# System_VoltageControl.net
KiCad netlist of a schematic drawn in Altium Designer
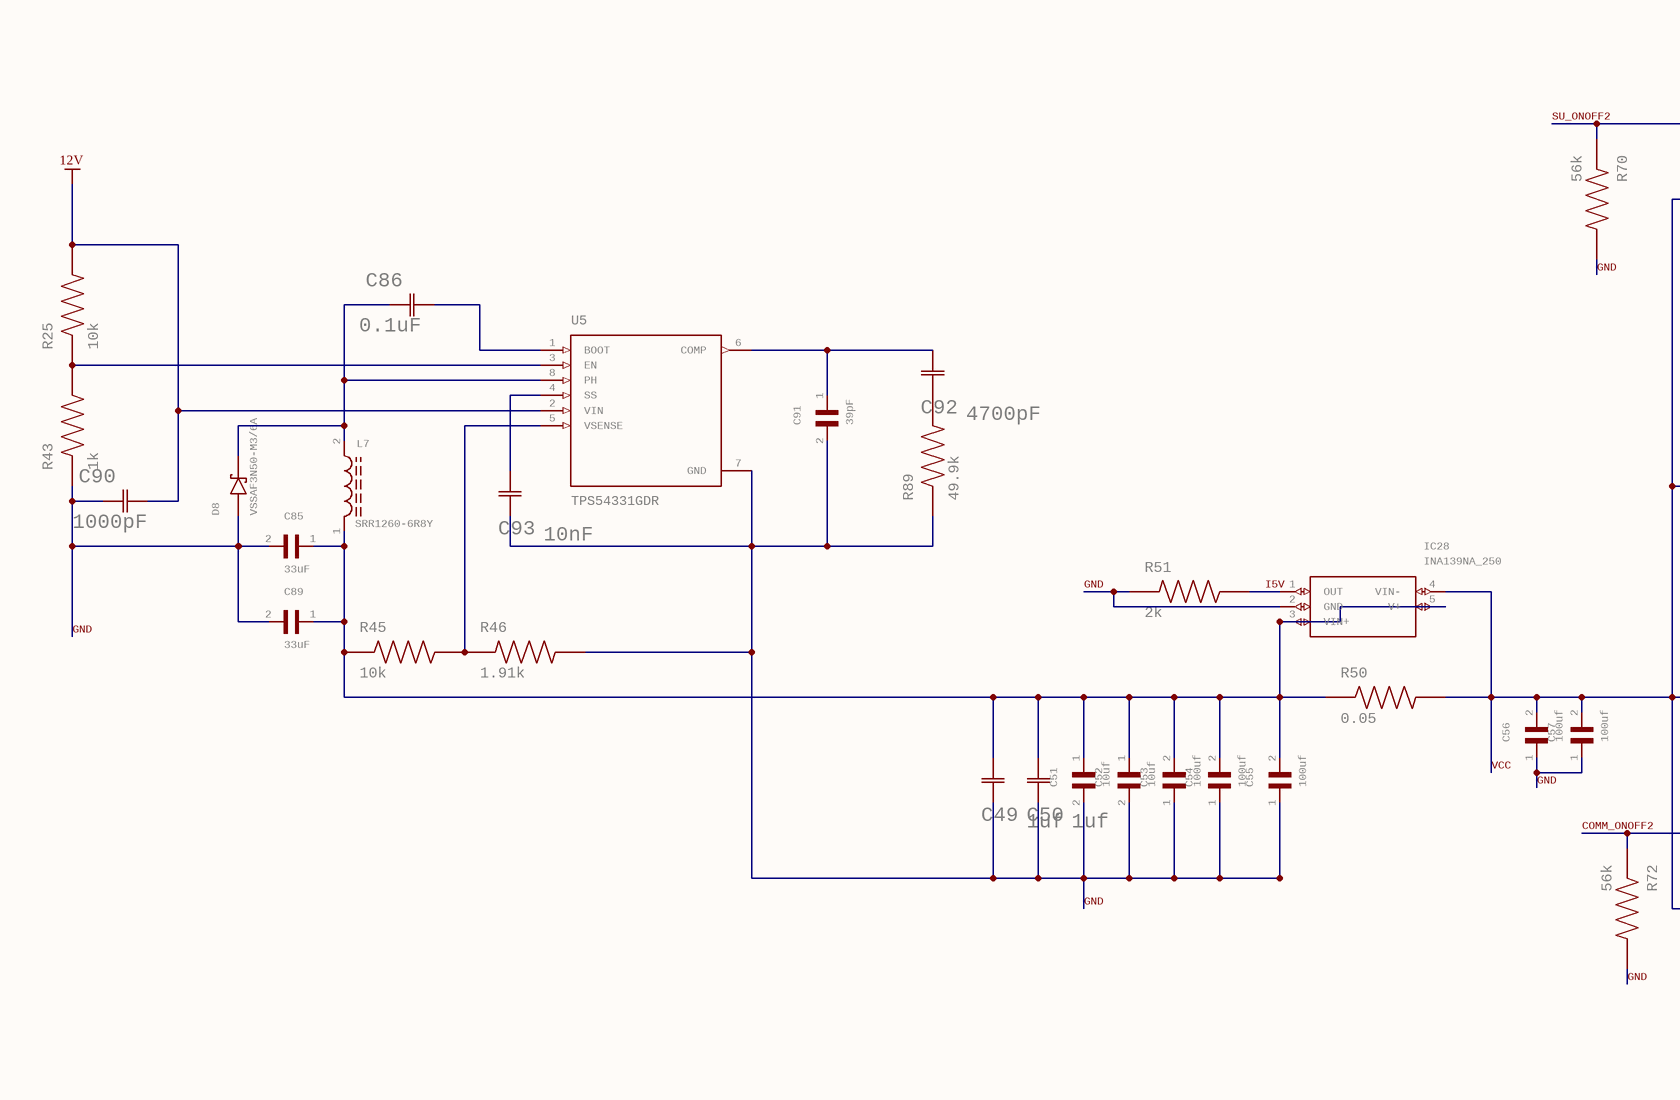
[diagram p0: System_VoltageControl.SchDoc, top left]
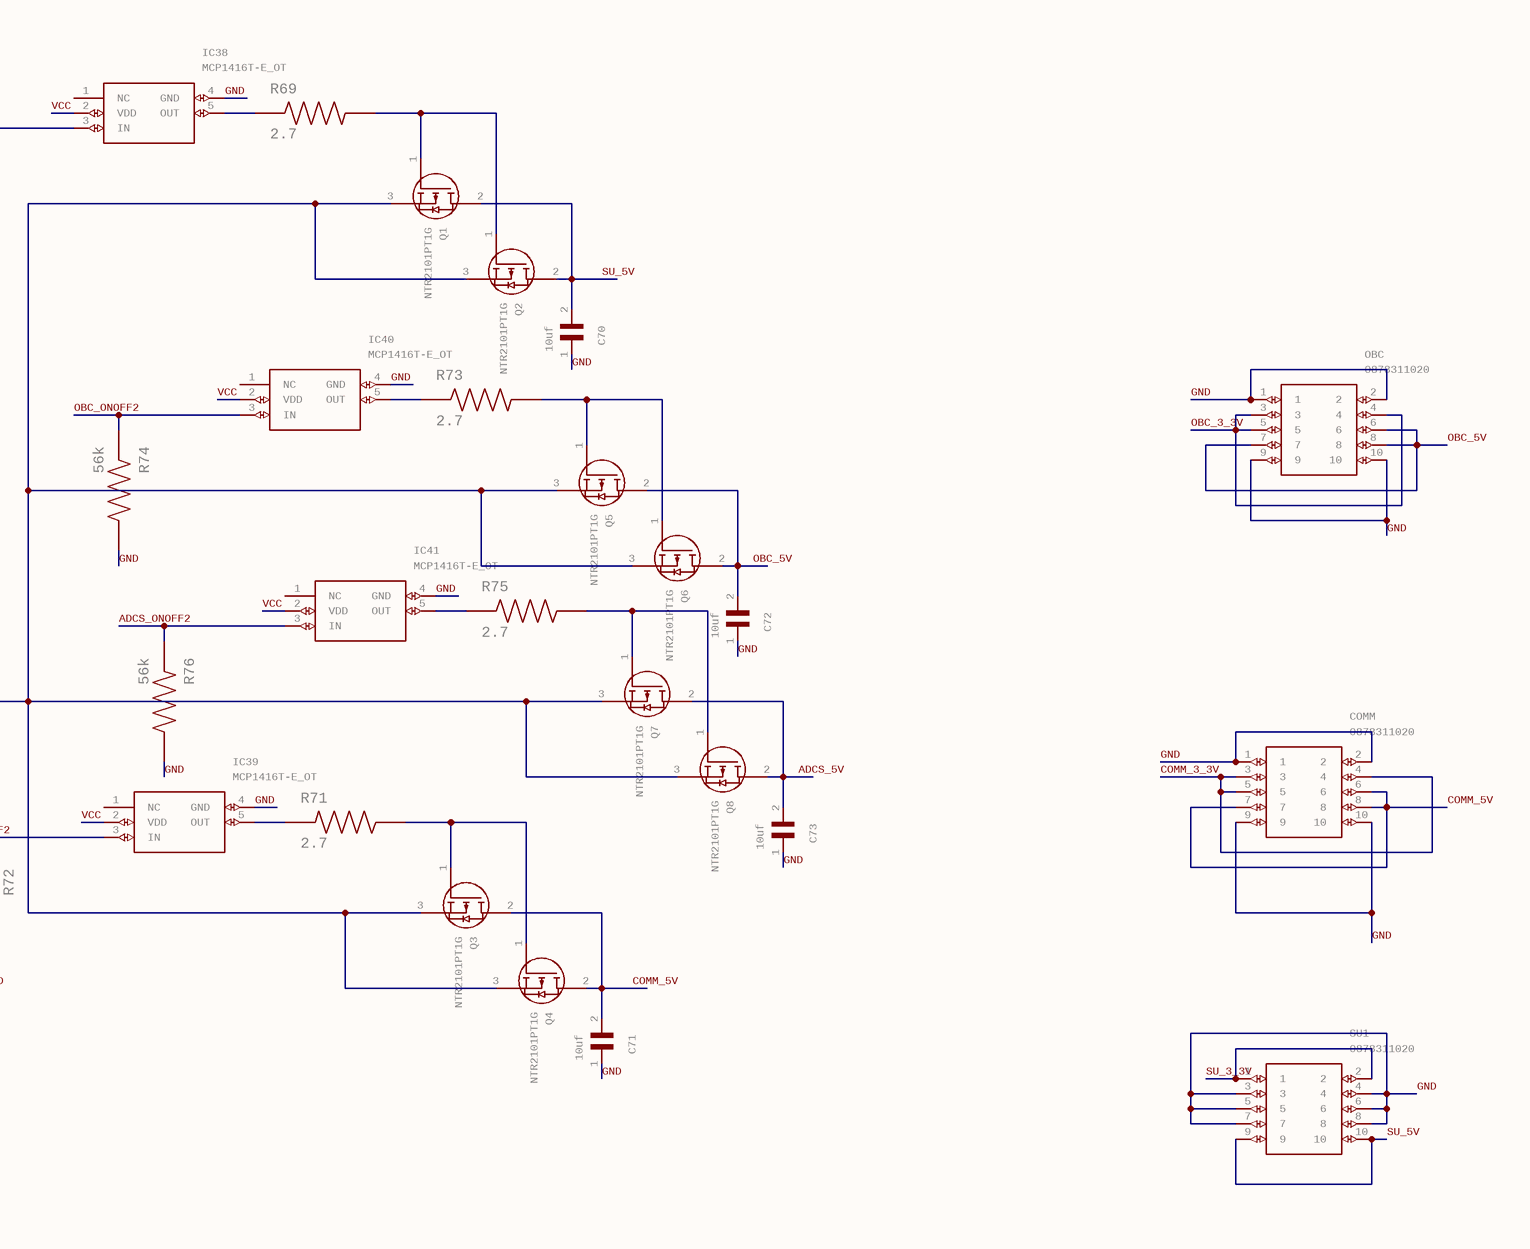
[diagram p1: System_VoltageControl.SchDoc, top right]
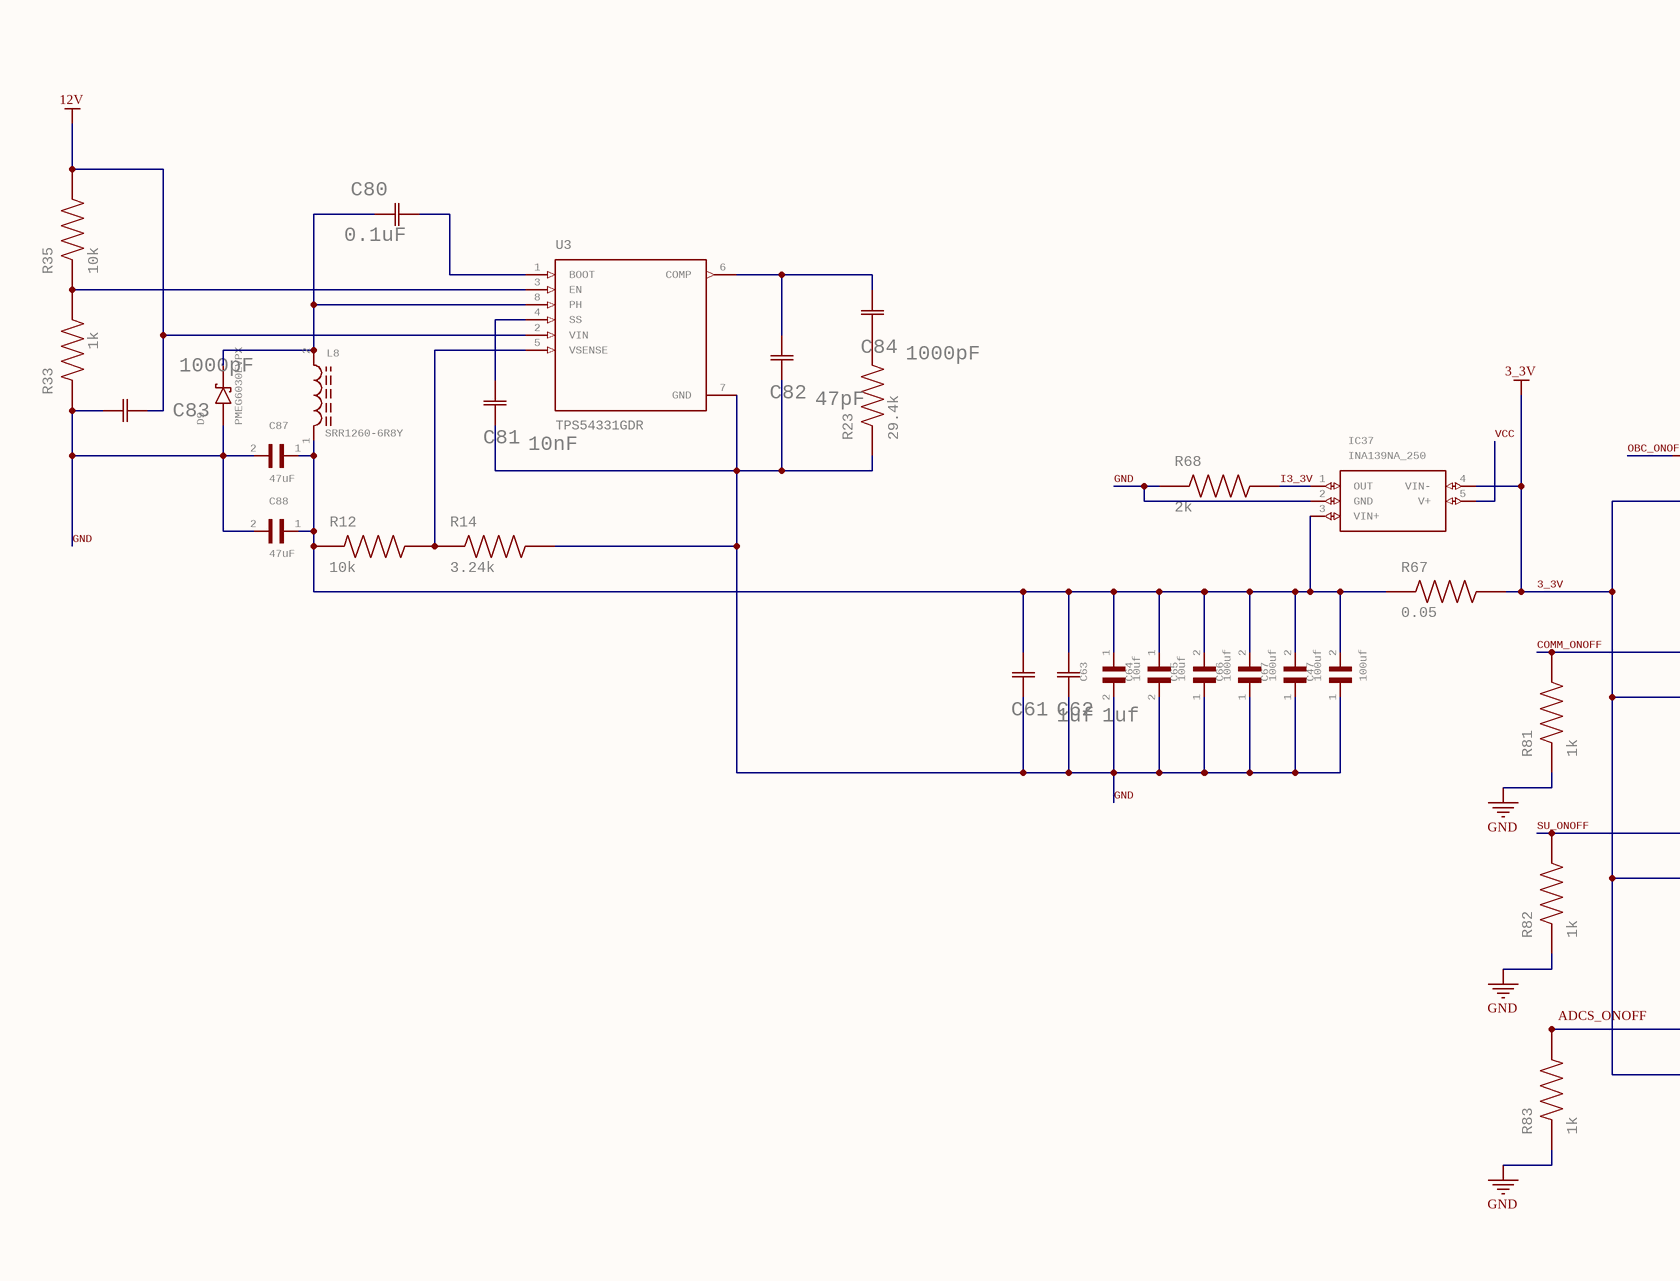
[diagram p2: System_VoltageControl.SchDoc, bottom left]
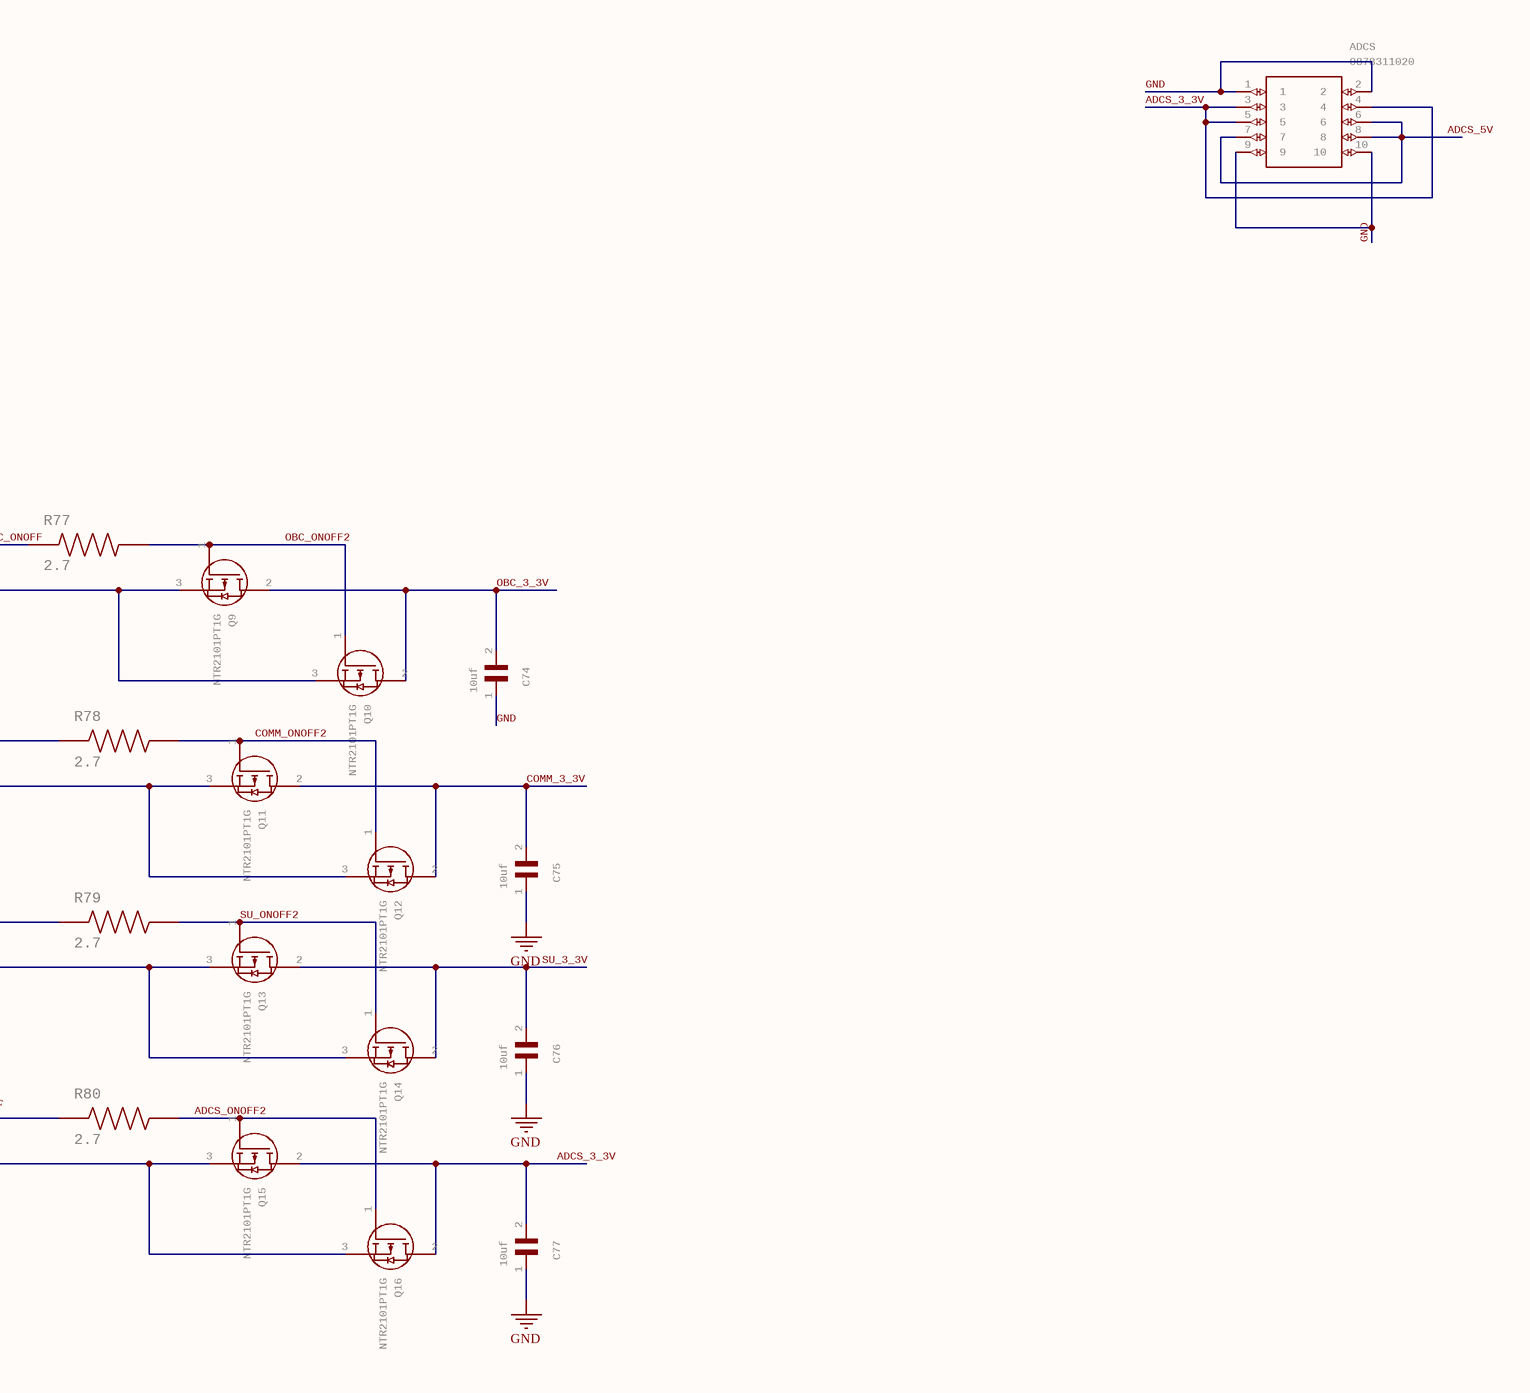
[diagram p3: System_VoltageControl.SchDoc, bottom right]

(export (version "E")
  (design (tool "Eeschema 10.0.6"))
  (components
    (comp (ref "ADCS")
      (value "0878311020")
      (footprint "SHDR10W55P200_2X5_1265X630X640")
      (description "Headers & Wire Housings 2.00MM HDR 02X05P VT TH 15AU   Source:  Datasheet")
      (libsource (lib "0878311020") (part "0878311020"))
    )
    (comp (ref "C47")
      (value "100uf")
      (footprint "CAPC3225X280N")
      (fields
        (field (name "DIGI-KEY_PART_NUMBER") "DIGI-KEY_PART_NUMBER")
        (field (name "MF") "KEMET")
        (field (name "MP") "C1210C107M4PAC7800")
      )
      (libsource (lib "Cap 100uf 16v") (part "C1210C107M4PAC7800"))
    )
    (comp (ref "C49")
      (value "1uf")
      (footprint "YAG_CC0603_YAG")
      (fields (field (name "MANUFACTURER_PART_NUMBER") "CC0603KRX7R7BB105"))
      (libsource (lib "Cap 1uf") (part "CC0603KRX7R7BB105"))
    )
    (comp (ref "C50")
      (value "1uf")
      (footprint "YAG_CC0603_YAG")
      (fields (field (name "MANUFACTURER_PART_NUMBER") "CC0603KRX7R7BB105"))
      (libsource (lib "Cap 1uf") (part "CC0603KRX7R7BB105"))
    )
    (comp (ref "C51")
      (value "10uf")
      (footprint "CAPC2012X70")
      (description "KC 10ÂµF 0805 10% 16V X5R")
      (fields (field (name "DIGI-KEY_PART_NUMBER") "311-1865-1-ND") (field (name "MF") "Yageo"))
      (libsource (lib "") (part "CC0805KKX5R7BB106_1"))
    )
    (comp (ref "C52")
      (value "10uf")
      (footprint "CAPC2012X70")
      (description "KC 10ÂµF 0805 10% 16V X5R")
      (fields (field (name "DIGI-KEY_PART_NUMBER") "311-1865-1-ND") (field (name "MF") "Yageo"))
      (libsource (lib "") (part "CC0805KKX5R7BB106_1"))
    )
    (comp (ref "C53")
      (value "100uf")
      (footprint "CAPC3225X280N")
      (fields
        (field (name "DIGI-KEY_PART_NUMBER") "DIGI-KEY_PART_NUMBER")
        (field (name "MF") "KEMET")
        (field (name "MP") "C1210C107M4PAC7800")
      )
      (libsource (lib "Cap 100uf 16v") (part "C1210C107M4PAC7800"))
    )
    (comp (ref "C54")
      (value "100uf")
      (footprint "CAPC3225X280N")
      (fields
        (field (name "DIGI-KEY_PART_NUMBER") "DIGI-KEY_PART_NUMBER")
        (field (name "MF") "KEMET")
        (field (name "MP") "C1210C107M4PAC7800")
      )
      (libsource (lib "Cap 100uf 16v") (part "C1210C107M4PAC7800"))
    )
    (comp (ref "C55")
      (value "100uf")
      (footprint "CAPC3225X280N")
      (fields
        (field (name "DIGI-KEY_PART_NUMBER") "DIGI-KEY_PART_NUMBER")
        (field (name "MF") "KEMET")
        (field (name "MP") "C1210C107M4PAC7800")
      )
      (libsource (lib "Cap 100uf 16v") (part "C1210C107M4PAC7800"))
    )
    (comp (ref "C56")
      (value "100uf")
      (footprint "CAPC3225X280N")
      (fields
        (field (name "DIGI-KEY_PART_NUMBER") "DIGI-KEY_PART_NUMBER")
        (field (name "MF") "KEMET")
        (field (name "MP") "C1210C107M4PAC7800")
      )
      (libsource (lib "Cap 100uf 16v") (part "C1210C107M4PAC7800"))
    )
    (comp (ref "C57")
      (value "100uf")
      (footprint "CAPC3225X280N")
      (fields
        (field (name "DIGI-KEY_PART_NUMBER") "DIGI-KEY_PART_NUMBER")
        (field (name "MF") "KEMET")
        (field (name "MP") "C1210C107M4PAC7800")
      )
      (libsource (lib "Cap 100uf 16v") (part "C1210C107M4PAC7800"))
    )
    (comp (ref "C61")
      (value "1uf")
      (footprint "YAG_CC0603_YAG")
      (fields (field (name "MANUFACTURER_PART_NUMBER") "CC0603KRX7R7BB105"))
      (libsource (lib "Cap 1uf") (part "CC0603KRX7R7BB105"))
    )
    (comp (ref "C62")
      (value "1uf")
      (footprint "YAG_CC0603_YAG")
      (fields (field (name "MANUFACTURER_PART_NUMBER") "CC0603KRX7R7BB105"))
      (libsource (lib "Cap 1uf") (part "CC0603KRX7R7BB105"))
    )
    (comp (ref "C63")
      (value "10uf")
      (footprint "CAPC2012X70")
      (description "KC 10ÂµF 0805 10% 16V X5R")
      (fields (field (name "DIGI-KEY_PART_NUMBER") "311-1865-1-ND") (field (name "MF") "Yageo"))
      (libsource (lib "") (part "CC0805KKX5R7BB106_1"))
    )
    (comp (ref "C64")
      (value "10uf")
      (footprint "CAPC2012X70")
      (description "KC 10ÂµF 0805 10% 16V X5R")
      (fields (field (name "DIGI-KEY_PART_NUMBER") "311-1865-1-ND") (field (name "MF") "Yageo"))
      (libsource (lib "") (part "CC0805KKX5R7BB106_1"))
    )
    (comp (ref "C65")
      (value "100uf")
      (footprint "CAPC3225X280N")
      (fields
        (field (name "DIGI-KEY_PART_NUMBER") "DIGI-KEY_PART_NUMBER")
        (field (name "MF") "KEMET")
        (field (name "MP") "C1210C107M4PAC7800")
      )
      (libsource (lib "Cap 100uf 16v") (part "C1210C107M4PAC7800"))
    )
    (comp (ref "C66")
      (value "100uf")
      (footprint "CAPC3225X280N")
      (fields
        (field (name "DIGI-KEY_PART_NUMBER") "DIGI-KEY_PART_NUMBER")
        (field (name "MF") "KEMET")
        (field (name "MP") "C1210C107M4PAC7800")
      )
      (libsource (lib "Cap 100uf 16v") (part "C1210C107M4PAC7800"))
    )
    (comp (ref "C67")
      (value "100uf")
      (footprint "CAPC3225X280N")
      (fields
        (field (name "DIGI-KEY_PART_NUMBER") "DIGI-KEY_PART_NUMBER")
        (field (name "MF") "KEMET")
        (field (name "MP") "C1210C107M4PAC7800")
      )
      (libsource (lib "Cap 100uf 16v") (part "C1210C107M4PAC7800"))
    )
    (comp (ref "C70")
      (value "10uf")
      (footprint "CAPC2012X70")
      (description "KC 10ÂµF 0805 10% 16V X5R")
      (fields (field (name "DIGI-KEY_PART_NUMBER") "311-1865-1-ND") (field (name "MF") "Yageo"))
      (libsource (lib "") (part "CC0805KKX5R7BB106_2"))
    )
    (comp (ref "C71")
      (value "10uf")
      (footprint "CAPC2012X70")
      (description "KC 10ÂµF 0805 10% 16V X5R")
      (fields (field (name "DIGI-KEY_PART_NUMBER") "311-1865-1-ND") (field (name "MF") "Yageo"))
      (libsource (lib "") (part "CC0805KKX5R7BB106_2"))
    )
    (comp (ref "C72")
      (value "10uf")
      (footprint "CAPC2012X70")
      (description "KC 10ÂµF 0805 10% 16V X5R")
      (fields (field (name "DIGI-KEY_PART_NUMBER") "311-1865-1-ND") (field (name "MF") "Yageo"))
      (libsource (lib "") (part "CC0805KKX5R7BB106_2"))
    )
    (comp (ref "C73")
      (value "10uf")
      (footprint "CAPC2012X70")
      (description "KC 10ÂµF 0805 10% 16V X5R")
      (fields (field (name "DIGI-KEY_PART_NUMBER") "311-1865-1-ND") (field (name "MF") "Yageo"))
      (libsource (lib "") (part "CC0805KKX5R7BB106_2"))
    )
    (comp (ref "C74")
      (value "10uf")
      (footprint "CAPC2012X70")
      (description "KC 10ÂµF 0805 10% 16V X5R")
      (fields (field (name "DIGI-KEY_PART_NUMBER") "311-1865-1-ND") (field (name "MF") "Yageo"))
      (libsource (lib "") (part "CC0805KKX5R7BB106_2"))
    )
    (comp (ref "C75")
      (value "10uf")
      (footprint "CAPC2012X70")
      (description "KC 10ÂµF 0805 10% 16V X5R")
      (fields (field (name "DIGI-KEY_PART_NUMBER") "311-1865-1-ND") (field (name "MF") "Yageo"))
      (libsource (lib "") (part "CC0805KKX5R7BB106_2"))
    )
    (comp (ref "C76")
      (value "10uf")
      (footprint "CAPC2012X70")
      (description "KC 10ÂµF 0805 10% 16V X5R")
      (fields (field (name "DIGI-KEY_PART_NUMBER") "311-1865-1-ND") (field (name "MF") "Yageo"))
      (libsource (lib "") (part "CC0805KKX5R7BB106_2"))
    )
    (comp (ref "C77")
      (value "10uf")
      (footprint "CAPC2012X70")
      (description "KC 10ÂµF 0805 10% 16V X5R")
      (fields (field (name "DIGI-KEY_PART_NUMBER") "311-1865-1-ND") (field (name "MF") "Yageo"))
      (libsource (lib "") (part "CC0805KKX5R7BB106_2"))
    )
    (comp (ref "C80")
      (value "0.1uF")
      (footprint "CC0603N_YAG")
      (fields (field (name "MANUFACTURER_PART_NUMBER") "CC0603KRX7R7BB104"))
      (libsource (lib "Cap 0.1uf") (part "CC0603KRX7R7BB104"))
    )
    (comp (ref "C81")
      (value "10nF")
      (footprint "CC0603N_YAG")
      (fields (field (name "MANUFACTURER_PART_NUMBER") "CC0603KRX7R7BB104"))
      (libsource (lib "Cap 0.1uf") (part "CC0603KRX7R7BB104"))
    )
    (comp (ref "C82")
      (value "47pF")
      (footprint "CC0603N_YAG")
      (fields (field (name "MANUFACTURER_PART_NUMBER") "CC0603KRX7R7BB104"))
      (libsource (lib "Cap 0.1uf") (part "CC0603KRX7R7BB104"))
    )
    (comp (ref "C83")
      (value "1000pF")
      (footprint "CC0603N_YAG")
      (fields (field (name "MANUFACTURER_PART_NUMBER") "CC0603KRX7R7BB104"))
      (libsource (lib "Cap 0.1uf") (part "CC0603KRX7R7BB104"))
    )
    (comp (ref "C84")
      (value "1000pF")
      (footprint "CC0603N_YAG")
      (fields (field (name "MANUFACTURER_PART_NUMBER") "CC0603KRX7R7BB104"))
      (libsource (lib "Cap 0.1uf") (part "CC0603KRX7R7BB104"))
    )
    (comp (ref "C85")
      (value "33uF")
      (footprint "CAPC2012X70")
      (description "KC 10ÂµF 0805 10% 16V X5R")
      (fields (field (name "DIGI-KEY_PART_NUMBER") "311-1865-1-ND") (field (name "MF") "Yageo"))
      (libsource (lib "Cap 10uf") (part "CC0805KKX5R7BB106"))
    )
    (comp (ref "C86")
      (value "0.1uF")
      (footprint "CC0603N_YAG")
      (fields (field (name "MANUFACTURER_PART_NUMBER") "CC0603KRX7R7BB104"))
      (libsource (lib "Cap 0.1uf") (part "CC0603KRX7R7BB104"))
    )
    (comp (ref "C87")
      (value "47uF")
      (footprint "CAPC2012X70")
      (description "KC 10ÂµF 0805 10% 16V X5R")
      (fields (field (name "DIGI-KEY_PART_NUMBER") "311-1865-1-ND") (field (name "MF") "Yageo"))
      (libsource (lib "Cap 10uf") (part "CC0805KKX5R7BB106"))
    )
    (comp (ref "C88")
      (value "47uF")
      (footprint "CAPC2012X70")
      (description "KC 10ÂµF 0805 10% 16V X5R")
      (fields (field (name "DIGI-KEY_PART_NUMBER") "311-1865-1-ND") (field (name "MF") "Yageo"))
      (libsource (lib "Cap 10uf") (part "CC0805KKX5R7BB106"))
    )
    (comp (ref "C89")
      (value "33uF")
      (footprint "CAPC2012X70")
      (description "KC 10ÂµF 0805 10% 16V X5R")
      (fields (field (name "DIGI-KEY_PART_NUMBER") "311-1865-1-ND") (field (name "MF") "Yageo"))
      (libsource (lib "Cap 10uf") (part "CC0805KKX5R7BB106"))
    )
    (comp (ref "C90")
      (value "1000pF")
      (footprint "CC0603N_YAG")
      (fields (field (name "MANUFACTURER_PART_NUMBER") "CC0603KRX7R7BB104"))
      (libsource (lib "Cap 0.1uf") (part "CC0603KRX7R7BB104"))
    )
    (comp (ref "C91")
      (value "39pF")
      (footprint "CAPC2012X70")
      (description "KC 10ÂµF 0805 10% 16V X5R")
      (fields (field (name "DIGI-KEY_PART_NUMBER") "311-1865-1-ND") (field (name "MF") "Yageo"))
      (libsource (lib "") (part "CC0805KKX5R7BB106_1"))
    )
    (comp (ref "C92")
      (value "4700pF")
      (footprint "CC0603N_YAG")
      (fields (field (name "MANUFACTURER_PART_NUMBER") "CC0603KRX7R7BB104"))
      (libsource (lib "Cap 0.1uf") (part "CC0603KRX7R7BB104"))
    )
    (comp (ref "C93")
      (value "10nF")
      (footprint "CC0603N_YAG")
      (fields (field (name "MANUFACTURER_PART_NUMBER") "CC0603KRX7R7BB104"))
      (libsource (lib "Cap 0.1uf") (part "CC0603KRX7R7BB104"))
    )
    (comp (ref "COMM")
      (value "0878311020")
      (footprint "SHDR10W55P200_2X5_1265X630X640")
      (description "Headers & Wire Housings 2.00MM HDR 02X05P VT TH 15AU   Source:  Datasheet")
      (libsource (lib "0878311020") (part "0878311020"))
    )
    (comp (ref "D8")
      (value "VSSAF3N50-M3/6A")
      (footprint "DIOM5226X100N")
      (description "Diode Schottky 50V 3A 2-Pin DO-221AC Plastic T/R Check prices")
      (fields (field (name "MF") "Vishay Semiconductor"))
      (libsource (lib "VSSAF3N50-M3_6A") (part "VSSAF3N50-M3/6A"))
    )
    (comp (ref "D9")
      (value "PMEG6030EVPX")
      (footprint "DIO_PMEG6030EVPX")
      (description "PMEG6030 Series 60 V 3 A Surface Mount Schottky Barrier Rectifier - SOD-128 Check prices")
      (fields (field (name "MF") "Nexperia USA"))
      (libsource (lib "PMEG6030EVPX") (part "PMEG6030EVPX"))
    )
    (comp (ref "IC28")
      (value "INA139NA_250")
      (footprint "SOT95P280X145-5N")
      (description "36V, High-Side, High-Speed, Current Output Current Sense Amplifier   Source:  Datasheet")
      (fields
        (field (name "ARROW_PART_NUMBER") "INA139NA/250")
        (field (name "MOUSER_PART_NUMBER") "595-INA139NA/250")
      )
      (libsource (lib "INA139NA_250") (part "INA139NA_250"))
    )
    (comp (ref "IC37")
      (value "INA139NA_250")
      (footprint "SOT95P280X145-5N")
      (description "36V, High-Side, High-Speed, Current Output Current Sense Amplifier   Source:  Datasheet")
      (fields
        (field (name "ARROW_PART_NUMBER") "INA139NA/250")
        (field (name "MOUSER_PART_NUMBER") "595-INA139NA/250")
      )
      (libsource (lib "INA139NA_250") (part "INA139NA_250"))
    )
    (comp (ref "IC38")
      (value "MCP1416T-E_OT")
      (footprint "SOT95P270X145-5N")
      (description "MOSFET Driver 1.5A High-Speed 18V SOT23   Source:  Datasheet")
      (fields
        (field (name "ARROW_PART_NUMBER") "MCP1416T-E/OT")
        (field (name "MOUSER_PART_NUMBER") "579-MCP1416T-E/OT")
      )
      (libsource (lib "MCP1416T-E_OT") (part "MCP1416T-E_OT"))
    )
    (comp (ref "IC39")
      (value "MCP1416T-E_OT")
      (footprint "SOT95P270X145-5N")
      (description "MOSFET Driver 1.5A High-Speed 18V SOT23   Source:  Datasheet")
      (fields
        (field (name "ARROW_PART_NUMBER") "MCP1416T-E/OT")
        (field (name "MOUSER_PART_NUMBER") "579-MCP1416T-E/OT")
      )
      (libsource (lib "MCP1416T-E_OT") (part "MCP1416T-E_OT"))
    )
    (comp (ref "IC40")
      (value "MCP1416T-E_OT")
      (footprint "SOT95P270X145-5N")
      (description "MOSFET Driver 1.5A High-Speed 18V SOT23   Source:  Datasheet")
      (fields
        (field (name "ARROW_PART_NUMBER") "MCP1416T-E/OT")
        (field (name "MOUSER_PART_NUMBER") "579-MCP1416T-E/OT")
      )
      (libsource (lib "MCP1416T-E_OT") (part "MCP1416T-E_OT"))
    )
    (comp (ref "IC41")
      (value "MCP1416T-E_OT")
      (footprint "SOT95P270X145-5N")
      (description "MOSFET Driver 1.5A High-Speed 18V SOT23   Source:  Datasheet")
      (fields
        (field (name "ARROW_PART_NUMBER") "MCP1416T-E/OT")
        (field (name "MOUSER_PART_NUMBER") "579-MCP1416T-E/OT")
      )
      (libsource (lib "MCP1416T-E_OT") (part "MCP1416T-E_OT"))
    )
    (comp (ref "L7")
      (value "SRR1260-6R8Y")
      (footprint "INDP125125X600N")
      (fields (field (name "MF") "Bourns") (field (name "MP") "SRR1260-150M"))
      (libsource (lib "SRR1260-150M") (part "SRR1260-150M"))
    )
    (comp (ref "L8")
      (value "SRR1260-6R8Y")
      (footprint "INDP125125X600N")
      (fields (field (name "MF") "Bourns") (field (name "MP") "SRR1260-150M"))
      (libsource (lib "SRR1260-150M") (part "SRR1260-150M"))
    )
    (comp (ref "OBC")
      (value "0878311020")
      (footprint "SHDR10W55P200_2X5_1265X630X640")
      (description "Headers & Wire Housings 2.00MM HDR 02X05P VT TH 15AU   Source:  Datasheet")
      (libsource (lib "0878311020") (part "0878311020"))
    )
    (comp (ref "Q1")
      (value "NTR2101PT1G")
      (footprint "SOT96P237X111-3N")
      (description "Small Signal MOSFET   Source:  Datasheet")
      (fields (field (name "MOUSER_PART_NUMBER") "863-NTR2101PT1G"))
      (libsource (lib "MOSFET-P") (part "NTR2101PT1G"))
    )
    (comp (ref "Q2")
      (value "NTR2101PT1G")
      (footprint "SOT96P237X111-3N")
      (description "Small Signal MOSFET   Source:  Datasheet")
      (fields (field (name "MOUSER_PART_NUMBER") "863-NTR2101PT1G"))
      (libsource (lib "MOSFET-P") (part "NTR2101PT1G"))
    )
    (comp (ref "Q3")
      (value "NTR2101PT1G")
      (footprint "SOT96P237X111-3N")
      (description "Small Signal MOSFET   Source:  Datasheet")
      (fields (field (name "MOUSER_PART_NUMBER") "863-NTR2101PT1G"))
      (libsource (lib "MOSFET-P") (part "NTR2101PT1G"))
    )
    (comp (ref "Q4")
      (value "NTR2101PT1G")
      (footprint "SOT96P237X111-3N")
      (description "Small Signal MOSFET   Source:  Datasheet")
      (fields (field (name "MOUSER_PART_NUMBER") "863-NTR2101PT1G"))
      (libsource (lib "MOSFET-P") (part "NTR2101PT1G"))
    )
    (comp (ref "Q5")
      (value "NTR2101PT1G")
      (footprint "SOT96P237X111-3N")
      (description "Small Signal MOSFET   Source:  Datasheet")
      (fields (field (name "MOUSER_PART_NUMBER") "863-NTR2101PT1G"))
      (libsource (lib "MOSFET-P") (part "NTR2101PT1G"))
    )
    (comp (ref "Q6")
      (value "NTR2101PT1G")
      (footprint "SOT96P237X111-3N")
      (description "Small Signal MOSFET   Source:  Datasheet")
      (fields (field (name "MOUSER_PART_NUMBER") "863-NTR2101PT1G"))
      (libsource (lib "MOSFET-P") (part "NTR2101PT1G"))
    )
    (comp (ref "Q7")
      (value "NTR2101PT1G")
      (footprint "SOT96P237X111-3N")
      (description "Small Signal MOSFET   Source:  Datasheet")
      (fields (field (name "MOUSER_PART_NUMBER") "863-NTR2101PT1G"))
      (libsource (lib "MOSFET-P") (part "NTR2101PT1G"))
    )
    (comp (ref "Q8")
      (value "NTR2101PT1G")
      (footprint "SOT96P237X111-3N")
      (description "Small Signal MOSFET   Source:  Datasheet")
      (fields (field (name "MOUSER_PART_NUMBER") "863-NTR2101PT1G"))
      (libsource (lib "MOSFET-P") (part "NTR2101PT1G"))
    )
    (comp (ref "Q9")
      (value "NTR2101PT1G")
      (footprint "SOT96P237X111-3N")
      (description "Small Signal MOSFET   Source:  Datasheet")
      (fields (field (name "MOUSER_PART_NUMBER") "863-NTR2101PT1G"))
      (libsource (lib "MOSFET-P") (part "NTR2101PT1G"))
    )
    (comp (ref "Q10")
      (value "NTR2101PT1G")
      (footprint "SOT96P237X111-3N")
      (description "Small Signal MOSFET   Source:  Datasheet")
      (fields (field (name "MOUSER_PART_NUMBER") "863-NTR2101PT1G"))
      (libsource (lib "MOSFET-P") (part "NTR2101PT1G"))
    )
    (comp (ref "Q11")
      (value "NTR2101PT1G")
      (footprint "SOT96P237X111-3N")
      (description "Small Signal MOSFET   Source:  Datasheet")
      (fields (field (name "MOUSER_PART_NUMBER") "863-NTR2101PT1G"))
      (libsource (lib "MOSFET-P") (part "NTR2101PT1G"))
    )
    (comp (ref "Q12")
      (value "NTR2101PT1G")
      (footprint "SOT96P237X111-3N")
      (description "Small Signal MOSFET   Source:  Datasheet")
      (fields (field (name "MOUSER_PART_NUMBER") "863-NTR2101PT1G"))
      (libsource (lib "MOSFET-P") (part "NTR2101PT1G"))
    )
    (comp (ref "Q13")
      (value "NTR2101PT1G")
      (footprint "SOT96P237X111-3N")
      (description "Small Signal MOSFET   Source:  Datasheet")
      (fields (field (name "MOUSER_PART_NUMBER") "863-NTR2101PT1G"))
      (libsource (lib "MOSFET-P") (part "NTR2101PT1G"))
    )
    (comp (ref "Q14")
      (value "NTR2101PT1G")
      (footprint "SOT96P237X111-3N")
      (description "Small Signal MOSFET   Source:  Datasheet")
      (fields (field (name "MOUSER_PART_NUMBER") "863-NTR2101PT1G"))
      (libsource (lib "MOSFET-P") (part "NTR2101PT1G"))
    )
    (comp (ref "Q15")
      (value "NTR2101PT1G")
      (footprint "SOT96P237X111-3N")
      (description "Small Signal MOSFET   Source:  Datasheet")
      (fields (field (name "MOUSER_PART_NUMBER") "863-NTR2101PT1G"))
      (libsource (lib "MOSFET-P") (part "NTR2101PT1G"))
    )
    (comp (ref "Q16")
      (value "NTR2101PT1G")
      (footprint "SOT96P237X111-3N")
      (description "Small Signal MOSFET   Source:  Datasheet")
      (fields (field (name "MOUSER_PART_NUMBER") "863-NTR2101PT1G"))
      (libsource (lib "MOSFET-P") (part "NTR2101PT1G"))
    )
    (comp (ref "R12")
      (value "10k")
      (footprint "RESC1608X55N")
      (fields
        (field (name "DIGI-KEY_PART_NUMBER") "DIGI-KEY_PART_NUMBER")
        (field (name "MF") "Susumu")
        (field (name "MP") "RL0816S-2R7-F")
      )
      (libsource (lib "Res1-2.7") (part "RL0816S-2R7-F"))
    )
    (comp (ref "R14")
      (value "3.24k")
      (footprint "RESC1608X55N")
      (fields
        (field (name "DIGI-KEY_PART_NUMBER") "DIGI-KEY_PART_NUMBER")
        (field (name "MF") "Susumu")
        (field (name "MP") "RL0816S-2R7-F")
      )
      (libsource (lib "Res1-2.7") (part "RL0816S-2R7-F"))
    )
    (comp (ref "R23")
      (value "29.4k")
      (footprint "RESC1608X55N")
      (fields
        (field (name "DIGI-KEY_PART_NUMBER") "DIGI-KEY_PART_NUMBER")
        (field (name "MF") "Susumu")
        (field (name "MP") "RL0816S-2R7-F")
      )
      (libsource (lib "Res1-2.7") (part "RL0816S-2R7-F"))
    )
    (comp (ref "R25")
      (value "10k")
      (footprint "RESC1608X55N")
      (fields
        (field (name "DIGI-KEY_PART_NUMBER") "DIGI-KEY_PART_NUMBER")
        (field (name "MF") "Susumu")
        (field (name "MP") "RL0816S-2R7-F")
      )
      (libsource (lib "Res1-2.7") (part "RL0816S-2R7-F"))
    )
    (comp (ref "R33")
      (value "1k")
      (footprint "RESC1608X55N")
      (fields
        (field (name "DIGI-KEY_PART_NUMBER") "DIGI-KEY_PART_NUMBER")
        (field (name "MF") "Susumu")
        (field (name "MP") "RL0816S-2R7-F")
      )
      (libsource (lib "Res1-2.7") (part "RL0816S-2R7-F"))
    )
    (comp (ref "R35")
      (value "10k")
      (footprint "RESC1608X55N")
      (fields
        (field (name "DIGI-KEY_PART_NUMBER") "DIGI-KEY_PART_NUMBER")
        (field (name "MF") "Susumu")
        (field (name "MP") "RL0816S-2R7-F")
      )
      (libsource (lib "Res1-2.7") (part "RL0816S-2R7-F"))
    )
    (comp (ref "R43")
      (value "1k")
      (footprint "RESC1608X55N")
      (fields
        (field (name "DIGI-KEY_PART_NUMBER") "DIGI-KEY_PART_NUMBER")
        (field (name "MF") "Susumu")
        (field (name "MP") "RL0816S-2R7-F")
      )
      (libsource (lib "Res1-2.7") (part "RL0816S-2R7-F"))
    )
    (comp (ref "R45")
      (value "10k")
      (footprint "RESC1608X55N")
      (fields
        (field (name "DIGI-KEY_PART_NUMBER") "DIGI-KEY_PART_NUMBER")
        (field (name "MF") "Susumu")
        (field (name "MP") "RL0816S-2R7-F")
      )
      (libsource (lib "Res1-2.7") (part "RL0816S-2R7-F"))
    )
    (comp (ref "R46")
      (value "1.91k")
      (footprint "RESC1608X55N")
      (fields
        (field (name "DIGI-KEY_PART_NUMBER") "DIGI-KEY_PART_NUMBER")
        (field (name "MF") "Susumu")
        (field (name "MP") "RL0816S-2R7-F")
      )
      (libsource (lib "Res1-2.7") (part "RL0816S-2R7-F"))
    )
    (comp (ref "R50")
      (value "0.05")
      (footprint "RESC1608X55N")
      (description "RES SMD 0.05 OHM 5% 1/5W 0603")
      (fields (field (name "DIGI-KEY_PART_NUMBER") "P50NJCT-ND") (field (name "MF") "Panasonic"))
      (libsource (lib "Res1 0.05") (part "ERJ-L03KJ50MV"))
    )
    (comp (ref "R51")
      (value "2k")
      (footprint "RESC1608X55N")
      (description "Res Thick Film 0603 2K Ohm 5% 0.2W(1/5W) Â±50ppm/C Pad SMD Automotive T/R")
      (fields (field (name "DIGI-KEY_PART_NUMBER") "P20315CT-ND") (field (name "MF") "Panasonic"))
      (libsource (lib "Res1 2k") (part "ERJ-PB3D2001V"))
    )
    (comp (ref "R67")
      (value "0.05")
      (footprint "RESC1608X55N")
      (description "RES SMD 0.05 OHM 5% 1/5W 0603")
      (fields (field (name "DIGI-KEY_PART_NUMBER") "P50NJCT-ND") (field (name "MF") "Panasonic"))
      (libsource (lib "Res1 0.05") (part "ERJ-L03KJ50MV"))
    )
    (comp (ref "R68")
      (value "2k")
      (footprint "RESC1608X55N")
      (description "Res Thick Film 0603 2K Ohm 5% 0.2W(1/5W) Â±50ppm/C Pad SMD Automotive T/R")
      (fields (field (name "DIGI-KEY_PART_NUMBER") "P20315CT-ND") (field (name "MF") "Panasonic"))
      (libsource (lib "Res1 2k") (part "ERJ-PB3D2001V"))
    )
    (comp (ref "R69")
      (value "2.7")
      (footprint "RESC1608X55N")
      (fields
        (field (name "DIGI-KEY_PART_NUMBER") "DIGI-KEY_PART_NUMBER")
        (field (name "MF") "Susumu")
        (field (name "MP") "RL0816S-2R7-F")
      )
      (libsource (lib "Res1-2.7") (part "RL0816S-2R7-F"))
    )
    (comp (ref "R70")
      (value "56k")
      (footprint "RESC1608X55N")
      (description "RES SMD 56K OHM 0.5% 1/5W 0603")
      (fields (field (name "DIGI-KEY_PART_NUMBER") "DIGI-KEY_PART_NUMBER") (field (name "MF") "Panasonic"))
      (libsource (lib "Res1 56k") (part "ERJ-PB3D5602V"))
    )
    (comp (ref "R71")
      (value "2.7")
      (footprint "RESC1608X55N")
      (fields
        (field (name "DIGI-KEY_PART_NUMBER") "DIGI-KEY_PART_NUMBER")
        (field (name "MF") "Susumu")
        (field (name "MP") "RL0816S-2R7-F")
      )
      (libsource (lib "Res1-2.7") (part "RL0816S-2R7-F"))
    )
    (comp (ref "R72")
      (value "56k")
      (footprint "RESC1608X55N")
      (description "RES SMD 56K OHM 0.5% 1/5W 0603")
      (fields (field (name "DIGI-KEY_PART_NUMBER") "DIGI-KEY_PART_NUMBER") (field (name "MF") "Panasonic"))
      (libsource (lib "Res1 56k") (part "ERJ-PB3D5602V"))
    )
    (comp (ref "R73")
      (value "2.7")
      (footprint "RESC1608X55N")
      (fields
        (field (name "DIGI-KEY_PART_NUMBER") "DIGI-KEY_PART_NUMBER")
        (field (name "MF") "Susumu")
        (field (name "MP") "RL0816S-2R7-F")
      )
      (libsource (lib "Res1-2.7") (part "RL0816S-2R7-F"))
    )
    (comp (ref "R74")
      (value "56k")
      (footprint "RESC1608X55N")
      (description "RES SMD 56K OHM 0.5% 1/5W 0603")
      (fields (field (name "DIGI-KEY_PART_NUMBER") "DIGI-KEY_PART_NUMBER") (field (name "MF") "Panasonic"))
      (libsource (lib "Res1 56k") (part "ERJ-PB3D5602V"))
    )
    (comp (ref "R75")
      (value "2.7")
      (footprint "RESC1608X55N")
      (fields
        (field (name "DIGI-KEY_PART_NUMBER") "DIGI-KEY_PART_NUMBER")
        (field (name "MF") "Susumu")
        (field (name "MP") "RL0816S-2R7-F")
      )
      (libsource (lib "Res1-2.7") (part "RL0816S-2R7-F"))
    )
    (comp (ref "R76")
      (value "56k")
      (footprint "RESC1608X55N")
      (description "RES SMD 56K OHM 0.5% 1/5W 0603")
      (fields (field (name "DIGI-KEY_PART_NUMBER") "DIGI-KEY_PART_NUMBER") (field (name "MF") "Panasonic"))
      (libsource (lib "Res1 56k") (part "ERJ-PB3D5602V"))
    )
    (comp (ref "R77")
      (value "2.7")
      (footprint "RESC1608X55N")
      (fields
        (field (name "DIGI-KEY_PART_NUMBER") "DIGI-KEY_PART_NUMBER")
        (field (name "MF") "Susumu")
        (field (name "MP") "RL0816S-2R7-F")
      )
      (libsource (lib "Res1-2.7") (part "RL0816S-2R7-F"))
    )
    (comp (ref "R78")
      (value "2.7")
      (footprint "RESC1608X55N")
      (fields
        (field (name "DIGI-KEY_PART_NUMBER") "DIGI-KEY_PART_NUMBER")
        (field (name "MF") "Susumu")
        (field (name "MP") "RL0816S-2R7-F")
      )
      (libsource (lib "Res1-2.7") (part "RL0816S-2R7-F"))
    )
    (comp (ref "R79")
      (value "2.7")
      (footprint "RESC1608X55N")
      (fields
        (field (name "DIGI-KEY_PART_NUMBER") "DIGI-KEY_PART_NUMBER")
        (field (name "MF") "Susumu")
        (field (name "MP") "RL0816S-2R7-F")
      )
      (libsource (lib "Res1-2.7") (part "RL0816S-2R7-F"))
    )
    (comp (ref "R80")
      (value "2.7")
      (footprint "RESC1608X55N")
      (fields
        (field (name "DIGI-KEY_PART_NUMBER") "DIGI-KEY_PART_NUMBER")
        (field (name "MF") "Susumu")
        (field (name "MP") "RL0816S-2R7-F")
      )
      (libsource (lib "Res1-2.7") (part "RL0816S-2R7-F"))
    )
    (comp (ref "R81")
      (value "1k")
      (footprint "RESC1608X55N")
      (description "Res Thick Film 0603 1K Ohm 5% 0.2W(1/5W) Â±50ppm/C Pad SMD Automotive T/R")
      (fields (field (name "DIGI-KEY_PART_NUMBER") "P20283CT-ND") (field (name "MF") "Panasonic"))
      (libsource (lib "Res1 1k") (part "ERJ-PB3D1001V"))
    )
    (comp (ref "R82")
      (value "1k")
      (footprint "RESC1608X55N")
      (description "Res Thick Film 0603 1K Ohm 5% 0.2W(1/5W) Â±50ppm/C Pad SMD Automotive T/R")
      (fields (field (name "DIGI-KEY_PART_NUMBER") "P20283CT-ND") (field (name "MF") "Panasonic"))
      (libsource (lib "Res1 1k") (part "ERJ-PB3D1001V"))
    )
    (comp (ref "R83")
      (value "1k")
      (footprint "RESC1608X55N")
      (description "Res Thick Film 0603 1K Ohm 5% 0.2W(1/5W) Â±50ppm/C Pad SMD Automotive T/R")
      (fields (field (name "DIGI-KEY_PART_NUMBER") "P20283CT-ND") (field (name "MF") "Panasonic"))
      (libsource (lib "Res1 1k") (part "ERJ-PB3D1001V"))
    )
    (comp (ref "R89")
      (value "49.9k")
      (footprint "RESC1608X55N")
      (fields
        (field (name "DIGI-KEY_PART_NUMBER") "DIGI-KEY_PART_NUMBER")
        (field (name "MF") "Susumu")
        (field (name "MP") "RL0816S-2R7-F")
      )
      (libsource (lib "Res1-2.7") (part "RL0816S-2R7-F"))
    )
    (comp (ref "SU1")
      (value "0878311020")
      (footprint "SHDR10W55P200_2X5_1265X630X640")
      (description "Headers & Wire Housings 2.00MM HDR 02X05P VT TH 15AU   Source:  Datasheet")
      (libsource (lib "0878311020") (part "0878311020"))
    )
    (comp (ref "U3")
      (value "TPS54331GDR")
      (footprint "SOIC127P599X175-8N")
      (description "Check prices")
      (fields (field (name "MF") "Texas Instruments"))
      (libsource (lib "TPS54331GDR") (part "TPS54331GDR"))
    )
    (comp (ref "U5")
      (value "TPS54331GDR")
      (footprint "SOIC127P599X175-8N")
      (description "Check prices")
      (fields (field (name "MF") "Texas Instruments"))
      (libsource (lib "TPS54331GDR") (part "TPS54331GDR"))
    )
  )
  (nets
    (net (code "1") (name "/ADCS_3_3V") (class "Default")
      (node (ref "ADCS") (pin "3") (pinfunction "3_3") (pintype "bidirectional"))
      (node (ref "ADCS") (pin "4") (pinfunction "4_4") (pintype "bidirectional"))
      (node (ref "ADCS") (pin "5") (pinfunction "5_5") (pintype "bidirectional"))
      (node (ref "C77") (pin "2") (pinfunction "2_2") (pintype "passive"))
      (node (ref "Q15") (pin "2") (pinfunction "S_2") (pintype "bidirectional"))
      (node (ref "Q16") (pin "2") (pinfunction "S_2") (pintype "bidirectional"))
    )
    (net (code "2") (name "/ADCS_5V") (class "Default")
      (node (ref "ADCS") (pin "6") (pinfunction "6_6") (pintype "bidirectional"))
      (node (ref "ADCS") (pin "7") (pinfunction "7_7") (pintype "bidirectional"))
      (node (ref "ADCS") (pin "8") (pinfunction "8_8") (pintype "bidirectional"))
      (node (ref "C73") (pin "2") (pinfunction "2_2") (pintype "passive"))
      (node (ref "Q7") (pin "2") (pinfunction "S_2") (pintype "bidirectional"))
      (node (ref "Q8") (pin "2") (pinfunction "S_2") (pintype "bidirectional"))
    )
    (net (code "4") (name "/ADCS_ONOFF2") (class "Default")
      (node (ref "IC41") (pin "3") (pinfunction "IN_3") (pintype "bidirectional"))
      (node (ref "Q15") (pin "1") (pinfunction "G_1") (pintype "bidirectional"))
      (node (ref "Q16") (pin "1") (pinfunction "G_1") (pintype "bidirectional"))
      (node (ref "R76") (pin "1") (pinfunction "1_1") (pintype "passive"))
      (node (ref "R80") (pin "2") (pinfunction "2_2") (pintype "passive"))
    )
    (net (code "5") (name "/COMM_3_3V") (class "Default")
      (node (ref "C75") (pin "2") (pinfunction "2_2") (pintype "passive"))
      (node (ref "COMM") (pin "3") (pinfunction "3_3") (pintype "bidirectional"))
      (node (ref "COMM") (pin "4") (pinfunction "4_4") (pintype "bidirectional"))
      (node (ref "COMM") (pin "5") (pinfunction "5_5") (pintype "bidirectional"))
      (node (ref "Q11") (pin "2") (pinfunction "S_2") (pintype "bidirectional"))
      (node (ref "Q12") (pin "2") (pinfunction "S_2") (pintype "bidirectional"))
    )
    (net (code "6") (name "/COMM_5V") (class "Default")
      (node (ref "C71") (pin "2") (pinfunction "2_2") (pintype "passive"))
      (node (ref "COMM") (pin "6") (pinfunction "6_6") (pintype "bidirectional"))
      (node (ref "COMM") (pin "7") (pinfunction "7_7") (pintype "bidirectional"))
      (node (ref "COMM") (pin "8") (pinfunction "8_8") (pintype "bidirectional"))
      (node (ref "Q3") (pin "2") (pinfunction "S_2") (pintype "bidirectional"))
      (node (ref "Q4") (pin "2") (pinfunction "S_2") (pintype "bidirectional"))
    )
    (net (code "7") (name "/COMM_ONOFF") (class "Default")
      (node (ref "R78") (pin "1") (pinfunction "1_1") (pintype "passive"))
      (node (ref "R81") (pin "2") (pinfunction "2_2") (pintype "passive"))
    )
    (net (code "8") (name "/COMM_ONOFF2") (class "Default")
      (node (ref "IC39") (pin "3") (pinfunction "IN_3") (pintype "bidirectional"))
      (node (ref "Q11") (pin "1") (pinfunction "G_1") (pintype "bidirectional"))
      (node (ref "Q12") (pin "1") (pinfunction "G_1") (pintype "bidirectional"))
      (node (ref "R72") (pin "1") (pinfunction "1_1") (pintype "passive"))
      (node (ref "R78") (pin "2") (pinfunction "2_2") (pintype "passive"))
    )
    (net (code "9") (name "/I3_3V") (class "Default")
      (node (ref "IC37") (pin "1") (pinfunction "OUT_1") (pintype "bidirectional"))
      (node (ref "R68") (pin "2") (pinfunction "2_2") (pintype "passive"))
    )
    (net (code "10") (name "/I5V") (class "Default")
      (node (ref "IC28") (pin "1") (pinfunction "OUT_1") (pintype "bidirectional"))
      (node (ref "R51") (pin "2") (pinfunction "2_2") (pintype "passive"))
    )
    (net (code "11") (name "/OBC_3_3V") (class "Default")
      (node (ref "C74") (pin "2") (pinfunction "2_2") (pintype "passive"))
      (node (ref "OBC") (pin "3") (pinfunction "3_3") (pintype "bidirectional"))
      (node (ref "OBC") (pin "4") (pinfunction "4_4") (pintype "bidirectional"))
      (node (ref "OBC") (pin "5") (pinfunction "5_5") (pintype "bidirectional"))
      (node (ref "Q10") (pin "2") (pinfunction "S_2") (pintype "bidirectional"))
      (node (ref "Q9") (pin "2") (pinfunction "S_2") (pintype "bidirectional"))
    )
    (net (code "12") (name "/OBC_5V") (class "Default")
      (node (ref "C72") (pin "2") (pinfunction "2_2") (pintype "passive"))
      (node (ref "OBC") (pin "6") (pinfunction "6_6") (pintype "bidirectional"))
      (node (ref "OBC") (pin "7") (pinfunction "7_7") (pintype "bidirectional"))
      (node (ref "OBC") (pin "8") (pinfunction "8_8") (pintype "bidirectional"))
      (node (ref "Q5") (pin "2") (pinfunction "S_2") (pintype "bidirectional"))
      (node (ref "Q6") (pin "2") (pinfunction "S_2") (pintype "bidirectional"))
    )
    (net (code "13") (name "/OBC_ONOFF") (class "Default")
      (node (ref "R77") (pin "1") (pinfunction "1_1") (pintype "passive"))
    )
    (net (code "14") (name "/OBC_ONOFF2") (class "Default")
      (node (ref "IC40") (pin "3") (pinfunction "IN_3") (pintype "bidirectional"))
      (node (ref "Q10") (pin "1") (pinfunction "G_1") (pintype "bidirectional"))
      (node (ref "Q9") (pin "1") (pinfunction "G_1") (pintype "bidirectional"))
      (node (ref "R74") (pin "1") (pinfunction "1_1") (pintype "passive"))
      (node (ref "R77") (pin "2") (pinfunction "2_2") (pintype "passive"))
    )
    (net (code "15") (name "/SU_3_3V") (class "Default")
      (node (ref "C76") (pin "2") (pinfunction "2_2") (pintype "passive"))
      (node (ref "Q13") (pin "2") (pinfunction "S_2") (pintype "bidirectional"))
      (node (ref "Q14") (pin "2") (pinfunction "S_2") (pintype "bidirectional"))
      (node (ref "SU1") (pin "1") (pinfunction "1_1") (pintype "bidirectional"))
      (node (ref "SU1") (pin "2") (pinfunction "2_2") (pintype "bidirectional"))
    )
    (net (code "16") (name "/SU_5V") (class "Default")
      (node (ref "C70") (pin "2") (pinfunction "2_2") (pintype "passive"))
      (node (ref "Q1") (pin "2") (pinfunction "S_2") (pintype "bidirectional"))
      (node (ref "Q2") (pin "2") (pinfunction "S_2") (pintype "bidirectional"))
      (node (ref "SU1") (pin "10") (pinfunction "10_10") (pintype "bidirectional"))
      (node (ref "SU1") (pin "9") (pinfunction "9_9") (pintype "bidirectional"))
    )
    (net (code "17") (name "/SU_ONOFF") (class "Default")
      (node (ref "R79") (pin "1") (pinfunction "1_1") (pintype "passive"))
      (node (ref "R82") (pin "2") (pinfunction "2_2") (pintype "passive"))
    )
    (net (code "18") (name "/SU_ONOFF2") (class "Default")
      (node (ref "IC38") (pin "3") (pinfunction "IN_3") (pintype "bidirectional"))
      (node (ref "Q13") (pin "1") (pinfunction "G_1") (pintype "bidirectional"))
      (node (ref "Q14") (pin "1") (pinfunction "G_1") (pintype "bidirectional"))
      (node (ref "R70") (pin "1") (pinfunction "1_1") (pintype "passive"))
      (node (ref "R79") (pin "2") (pinfunction "2_2") (pintype "passive"))
    )
    (net (code "19") (name "/VCC") (class "Default")
      (node (ref "C56") (pin "2") (pinfunction "2_2") (pintype "passive"))
      (node (ref "C57") (pin "2") (pinfunction "2_2") (pintype "passive"))
      (node (ref "IC28") (pin "4") (pinfunction "VIN-_4") (pintype "bidirectional"))
      (node (ref "IC37") (pin "5") (pinfunction "V+_5") (pintype "bidirectional"))
      (node (ref "IC38") (pin "2") (pinfunction "VDD_2") (pintype "bidirectional"))
      (node (ref "IC39") (pin "2") (pinfunction "VDD_2") (pintype "bidirectional"))
      (node (ref "IC40") (pin "2") (pinfunction "VDD_2") (pintype "bidirectional"))
      (node (ref "IC41") (pin "2") (pinfunction "VDD_2") (pintype "bidirectional"))
      (node (ref "Q1") (pin "3") (pinfunction "D_3") (pintype "bidirectional"))
      (node (ref "Q2") (pin "3") (pinfunction "D_3") (pintype "bidirectional"))
      (node (ref "Q3") (pin "3") (pinfunction "D_3") (pintype "bidirectional"))
      (node (ref "Q4") (pin "3") (pinfunction "D_3") (pintype "bidirectional"))
      (node (ref "Q5") (pin "3") (pinfunction "D_3") (pintype "bidirectional"))
      (node (ref "Q6") (pin "3") (pinfunction "D_3") (pintype "bidirectional"))
      (node (ref "Q7") (pin "3") (pinfunction "D_3") (pintype "bidirectional"))
      (node (ref "Q8") (pin "3") (pinfunction "D_3") (pintype "bidirectional"))
      (node (ref "R50") (pin "2") (pinfunction "2_2") (pintype "passive"))
    )
    (net (code "20") (name "3_3V") (class "Default")
      (node (ref "IC37") (pin "4") (pinfunction "VIN-_4") (pintype "bidirectional"))
      (node (ref "Q10") (pin "3") (pinfunction "D_3") (pintype "bidirectional"))
      (node (ref "Q11") (pin "3") (pinfunction "D_3") (pintype "bidirectional"))
      (node (ref "Q12") (pin "3") (pinfunction "D_3") (pintype "bidirectional"))
      (node (ref "Q13") (pin "3") (pinfunction "D_3") (pintype "bidirectional"))
      (node (ref "Q14") (pin "3") (pinfunction "D_3") (pintype "bidirectional"))
      (node (ref "Q15") (pin "3") (pinfunction "D_3") (pintype "bidirectional"))
      (node (ref "Q16") (pin "3") (pinfunction "D_3") (pintype "bidirectional"))
      (node (ref "Q9") (pin "3") (pinfunction "D_3") (pintype "bidirectional"))
      (node (ref "R67") (pin "2") (pinfunction "2_2") (pintype "passive"))
    )
    (net (code "21") (name "12V") (class "Default")
      (node (ref "C83") (pin "1") (pinfunction "1_1") (pintype "passive"))
      (node (ref "C90") (pin "2") (pinfunction "2_2") (pintype "passive"))
      (node (ref "R25") (pin "2") (pinfunction "2_2") (pintype "passive"))
      (node (ref "R35") (pin "2") (pinfunction "2_2") (pintype "passive"))
      (node (ref "U3") (pin "2") (pinfunction "VIN_2") (pintype "input"))
      (node (ref "U5") (pin "2") (pinfunction "VIN_2") (pintype "input"))
    )
    (net (code "22") (name "GND") (class "Default")
      (node (ref "ADCS") (pin "1") (pinfunction "1_1") (pintype "bidirectional"))
      (node (ref "ADCS") (pin "10") (pinfunction "10_10") (pintype "bidirectional"))
      (node (ref "ADCS") (pin "2") (pinfunction "2_2") (pintype "bidirectional"))
      (node (ref "ADCS") (pin "9") (pinfunction "9_9") (pintype "bidirectional"))
      (node (ref "C47") (pin "1") (pinfunction "1_1") (pintype "passive"))
      (node (ref "C49") (pin "1") (pinfunction "1_1") (pintype "passive"))
      (node (ref "C50") (pin "1") (pinfunction "1_1") (pintype "passive"))
      (node (ref "C51") (pin "2") (pinfunction "2_2") (pintype "passive"))
      (node (ref "C52") (pin "2") (pinfunction "2_2") (pintype "passive"))
      (node (ref "C53") (pin "1") (pinfunction "1_1") (pintype "passive"))
      (node (ref "C54") (pin "1") (pinfunction "1_1") (pintype "passive"))
      (node (ref "C55") (pin "1") (pinfunction "1_1") (pintype "passive"))
      (node (ref "C56") (pin "1") (pinfunction "1_1") (pintype "passive"))
      (node (ref "C57") (pin "1") (pinfunction "1_1") (pintype "passive"))
      (node (ref "C61") (pin "1") (pinfunction "1_1") (pintype "passive"))
      (node (ref "C62") (pin "1") (pinfunction "1_1") (pintype "passive"))
      (node (ref "C63") (pin "2") (pinfunction "2_2") (pintype "passive"))
      (node (ref "C64") (pin "2") (pinfunction "2_2") (pintype "passive"))
      (node (ref "C65") (pin "1") (pinfunction "1_1") (pintype "passive"))
      (node (ref "C66") (pin "1") (pinfunction "1_1") (pintype "passive"))
      (node (ref "C67") (pin "1") (pinfunction "1_1") (pintype "passive"))
      (node (ref "C70") (pin "1") (pinfunction "1_1") (pintype "passive"))
      (node (ref "C71") (pin "1") (pinfunction "1_1") (pintype "passive"))
      (node (ref "C72") (pin "1") (pinfunction "1_1") (pintype "passive"))
      (node (ref "C73") (pin "1") (pinfunction "1_1") (pintype "passive"))
      (node (ref "C74") (pin "1") (pinfunction "1_1") (pintype "passive"))
      (node (ref "C75") (pin "1") (pinfunction "1_1") (pintype "passive"))
      (node (ref "C76") (pin "1") (pinfunction "1_1") (pintype "passive"))
      (node (ref "C77") (pin "1") (pinfunction "1_1") (pintype "passive"))
      (node (ref "C81") (pin "1") (pinfunction "1_1") (pintype "passive"))
      (node (ref "C82") (pin "1") (pinfunction "1_1") (pintype "passive"))
      (node (ref "C83") (pin "2") (pinfunction "2_2") (pintype "passive"))
      (node (ref "C85") (pin "2") (pinfunction "2_2") (pintype "passive"))
      (node (ref "C87") (pin "2") (pinfunction "2_2") (pintype "passive"))
      (node (ref "C88") (pin "2") (pinfunction "2_2") (pintype "passive"))
      (node (ref "C89") (pin "2") (pinfunction "2_2") (pintype "passive"))
      (node (ref "C90") (pin "1") (pinfunction "1_1") (pintype "passive"))
      (node (ref "C91") (pin "2") (pinfunction "2_2") (pintype "passive"))
      (node (ref "C93") (pin "1") (pinfunction "1_1") (pintype "passive"))
      (node (ref "COMM") (pin "1") (pinfunction "1_1") (pintype "bidirectional"))
      (node (ref "COMM") (pin "10") (pinfunction "10_10") (pintype "bidirectional"))
      (node (ref "COMM") (pin "2") (pinfunction "2_2") (pintype "bidirectional"))
      (node (ref "COMM") (pin "9") (pinfunction "9_9") (pintype "bidirectional"))
      (node (ref "D8") (pin "A") (pinfunction "A_A") (pintype "passive"))
      (node (ref "D9") (pin "2") (pinfunction "A_2") (pintype "passive"))
      (node (ref "IC28") (pin "2") (pinfunction "GND_2") (pintype "bidirectional"))
      (node (ref "IC37") (pin "2") (pinfunction "GND_2") (pintype "bidirectional"))
      (node (ref "IC38") (pin "4") (pinfunction "GND_4") (pintype "bidirectional"))
      (node (ref "IC39") (pin "4") (pinfunction "GND_4") (pintype "bidirectional"))
      (node (ref "IC40") (pin "4") (pinfunction "GND_4") (pintype "bidirectional"))
      (node (ref "IC41") (pin "4") (pinfunction "GND_4") (pintype "bidirectional"))
      (node (ref "OBC") (pin "1") (pinfunction "1_1") (pintype "bidirectional"))
      (node (ref "OBC") (pin "10") (pinfunction "10_10") (pintype "bidirectional"))
      (node (ref "OBC") (pin "2") (pinfunction "2_2") (pintype "bidirectional"))
      (node (ref "OBC") (pin "9") (pinfunction "9_9") (pintype "bidirectional"))
      (node (ref "R14") (pin "2") (pinfunction "2_2") (pintype "passive"))
      (node (ref "R23") (pin "1") (pinfunction "1_1") (pintype "passive"))
      (node (ref "R33") (pin "1") (pinfunction "1_1") (pintype "passive"))
      (node (ref "R43") (pin "1") (pinfunction "1_1") (pintype "passive"))
      (node (ref "R46") (pin "2") (pinfunction "2_2") (pintype "passive"))
      (node (ref "R51") (pin "1") (pinfunction "1_1") (pintype "passive"))
      (node (ref "R68") (pin "1") (pinfunction "1_1") (pintype "passive"))
      (node (ref "R70") (pin "2") (pinfunction "2_2") (pintype "passive"))
      (node (ref "R72") (pin "2") (pinfunction "2_2") (pintype "passive"))
      (node (ref "R74") (pin "2") (pinfunction "2_2") (pintype "passive"))
      (node (ref "R76") (pin "2") (pinfunction "2_2") (pintype "passive"))
      (node (ref "R81") (pin "1") (pinfunction "1_1") (pintype "passive"))
      (node (ref "R82") (pin "1") (pinfunction "1_1") (pintype "passive"))
      (node (ref "R83") (pin "1") (pinfunction "1_1") (pintype "passive"))
      (node (ref "R89") (pin "1") (pinfunction "1_1") (pintype "passive"))
      (node (ref "SU1") (pin "3") (pinfunction "3_3") (pintype "bidirectional"))
      (node (ref "SU1") (pin "4") (pinfunction "4_4") (pintype "bidirectional"))
      (node (ref "SU1") (pin "5") (pinfunction "5_5") (pintype "bidirectional"))
      (node (ref "SU1") (pin "6") (pinfunction "6_6") (pintype "bidirectional"))
      (node (ref "SU1") (pin "7") (pinfunction "7_7") (pintype "bidirectional"))
      (node (ref "SU1") (pin "8") (pinfunction "8_8") (pintype "bidirectional"))
      (node (ref "U3") (pin "7") (pinfunction "GND_7") (pintype "power_in"))
      (node (ref "U5") (pin "7") (pinfunction "GND_7") (pintype "power_in"))
    )
    (net (code "23") (name "Net-(C84-Pad1)") (class "Default")
      (node (ref "C84") (pin "1") (pinfunction "1_1") (pintype "passive"))
      (node (ref "R23") (pin "2") (pinfunction "2_2") (pintype "passive"))
    )
    (net (code "24") (name "Net-(C92-Pad1)") (class "Default")
      (node (ref "C92") (pin "1") (pinfunction "1_1") (pintype "passive"))
      (node (ref "R89") (pin "2") (pinfunction "2_2") (pintype "passive"))
    )
    (net (code "25") (name "Net-(D8-K)") (class "Default")
      (node (ref "C86") (pin "1") (pinfunction "1_1") (pintype "passive"))
      (node (ref "D8") (pin "C") (pinfunction "K_C") (pintype "passive"))
      (node (ref "L7") (pin "2") (pinfunction "2_2") (pintype "passive"))
      (node (ref "U5") (pin "8") (pinfunction "PH_8") (pintype "input"))
    )
    (net (code "26") (name "Net-(D9-K)") (class "Default")
      (node (ref "C80") (pin "1") (pinfunction "1_1") (pintype "passive"))
      (node (ref "D9") (pin "1") (pinfunction "K_1") (pintype "passive"))
      (node (ref "L8") (pin "2") (pinfunction "2_2") (pintype "passive"))
      (node (ref "U3") (pin "8") (pinfunction "PH_8") (pintype "input"))
    )
    (net (code "27") (name "Net-(IC28-V+)") (class "Default")
      (node (ref "C49") (pin "2") (pinfunction "2_2") (pintype "passive"))
      (node (ref "C50") (pin "2") (pinfunction "2_2") (pintype "passive"))
      (node (ref "C51") (pin "1") (pinfunction "1_1") (pintype "passive"))
      (node (ref "C52") (pin "1") (pinfunction "1_1") (pintype "passive"))
      (node (ref "C53") (pin "2") (pinfunction "2_2") (pintype "passive"))
      (node (ref "C54") (pin "2") (pinfunction "2_2") (pintype "passive"))
      (node (ref "C55") (pin "2") (pinfunction "2_2") (pintype "passive"))
      (node (ref "C85") (pin "1") (pinfunction "1_1") (pintype "passive"))
      (node (ref "C89") (pin "1") (pinfunction "1_1") (pintype "passive"))
      (node (ref "IC28") (pin "3") (pinfunction "VIN+_3") (pintype "bidirectional"))
      (node (ref "IC28") (pin "5") (pinfunction "V+_5") (pintype "bidirectional"))
      (node (ref "L7") (pin "1") (pinfunction "1_1") (pintype "passive"))
      (node (ref "R45") (pin "1") (pinfunction "1_1") (pintype "passive"))
      (node (ref "R50") (pin "1") (pinfunction "1_1") (pintype "passive"))
    )
    (net (code "28") (name "Net-(IC37-VIN+)") (class "Default")
      (node (ref "C47") (pin "2") (pinfunction "2_2") (pintype "passive"))
      (node (ref "C61") (pin "2") (pinfunction "2_2") (pintype "passive"))
      (node (ref "C62") (pin "2") (pinfunction "2_2") (pintype "passive"))
      (node (ref "C63") (pin "1") (pinfunction "1_1") (pintype "passive"))
      (node (ref "C64") (pin "1") (pinfunction "1_1") (pintype "passive"))
      (node (ref "C65") (pin "2") (pinfunction "2_2") (pintype "passive"))
      (node (ref "C66") (pin "2") (pinfunction "2_2") (pintype "passive"))
      (node (ref "C67") (pin "2") (pinfunction "2_2") (pintype "passive"))
      (node (ref "C87") (pin "1") (pinfunction "1_1") (pintype "passive"))
      (node (ref "C88") (pin "1") (pinfunction "1_1") (pintype "passive"))
      (node (ref "IC37") (pin "3") (pinfunction "VIN+_3") (pintype "bidirectional"))
      (node (ref "L8") (pin "1") (pinfunction "1_1") (pintype "passive"))
      (node (ref "R12") (pin "1") (pinfunction "1_1") (pintype "passive"))
      (node (ref "R67") (pin "1") (pinfunction "1_1") (pintype "passive"))
    )
    (net (code "29") (name "Net-(IC38-OUT)") (class "Default")
      (node (ref "IC38") (pin "5") (pinfunction "OUT_5") (pintype "bidirectional"))
      (node (ref "R69") (pin "1") (pinfunction "1_1") (pintype "passive"))
    )
    (net (code "30") (name "Net-(IC39-OUT)") (class "Default")
      (node (ref "IC39") (pin "5") (pinfunction "OUT_5") (pintype "bidirectional"))
      (node (ref "R71") (pin "1") (pinfunction "1_1") (pintype "passive"))
    )
    (net (code "31") (name "Net-(IC40-OUT)") (class "Default")
      (node (ref "IC40") (pin "5") (pinfunction "OUT_5") (pintype "bidirectional"))
      (node (ref "R73") (pin "1") (pinfunction "1_1") (pintype "passive"))
    )
    (net (code "32") (name "Net-(IC41-OUT)") (class "Default")
      (node (ref "IC41") (pin "5") (pinfunction "OUT_5") (pintype "bidirectional"))
      (node (ref "R75") (pin "1") (pinfunction "1_1") (pintype "passive"))
    )
    (net (code "33") (name "Net-(Q1-G)") (class "Default")
      (node (ref "Q1") (pin "1") (pinfunction "G_1") (pintype "bidirectional"))
      (node (ref "Q2") (pin "1") (pinfunction "G_1") (pintype "bidirectional"))
      (node (ref "R69") (pin "2") (pinfunction "2_2") (pintype "passive"))
    )
    (net (code "34") (name "Net-(Q3-G)") (class "Default")
      (node (ref "Q3") (pin "1") (pinfunction "G_1") (pintype "bidirectional"))
      (node (ref "Q4") (pin "1") (pinfunction "G_1") (pintype "bidirectional"))
      (node (ref "R71") (pin "2") (pinfunction "2_2") (pintype "passive"))
    )
    (net (code "35") (name "Net-(Q5-G)") (class "Default")
      (node (ref "Q5") (pin "1") (pinfunction "G_1") (pintype "bidirectional"))
      (node (ref "Q6") (pin "1") (pinfunction "G_1") (pintype "bidirectional"))
      (node (ref "R73") (pin "2") (pinfunction "2_2") (pintype "passive"))
    )
    (net (code "36") (name "Net-(Q7-G)") (class "Default")
      (node (ref "Q7") (pin "1") (pinfunction "G_1") (pintype "bidirectional"))
      (node (ref "Q8") (pin "1") (pinfunction "G_1") (pintype "bidirectional"))
      (node (ref "R75") (pin "2") (pinfunction "2_2") (pintype "passive"))
    )
    (net (code "37") (name "Net-(R80-Pad1)") (class "Default")
      (node (ref "R80") (pin "1") (pinfunction "1_1") (pintype "passive"))
      (node (ref "R83") (pin "2") (pinfunction "2_2") (pintype "passive"))
    )
    (net (code "38") (name "Net-(U3-BOOT)") (class "Default")
      (node (ref "C80") (pin "2") (pinfunction "2_2") (pintype "passive"))
      (node (ref "U3") (pin "1") (pinfunction "BOOT_1") (pintype "input"))
    )
    (net (code "39") (name "Net-(U3-COMP)") (class "Default")
      (node (ref "C82") (pin "2") (pinfunction "2_2") (pintype "passive"))
      (node (ref "C84") (pin "2") (pinfunction "2_2") (pintype "passive"))
      (node (ref "U3") (pin "6") (pinfunction "COMP_6") (pintype "output"))
    )
    (net (code "40") (name "Net-(U3-EN)") (class "Default")
      (node (ref "R33") (pin "2") (pinfunction "2_2") (pintype "passive"))
      (node (ref "R35") (pin "1") (pinfunction "1_1") (pintype "passive"))
      (node (ref "U3") (pin "3") (pinfunction "EN_3") (pintype "input"))
    )
    (net (code "41") (name "Net-(U3-SS)") (class "Default")
      (node (ref "C81") (pin "2") (pinfunction "2_2") (pintype "passive"))
      (node (ref "U3") (pin "4") (pinfunction "SS_4") (pintype "input"))
    )
    (net (code "42") (name "Net-(U3-VSENSE)") (class "Default")
      (node (ref "R12") (pin "2") (pinfunction "2_2") (pintype "passive"))
      (node (ref "R14") (pin "1") (pinfunction "1_1") (pintype "passive"))
      (node (ref "U3") (pin "5") (pinfunction "VSENSE_5") (pintype "input"))
    )
    (net (code "43") (name "Net-(U5-BOOT)") (class "Default")
      (node (ref "C86") (pin "2") (pinfunction "2_2") (pintype "passive"))
      (node (ref "U5") (pin "1") (pinfunction "BOOT_1") (pintype "input"))
    )
    (net (code "44") (name "Net-(U5-COMP)") (class "Default")
      (node (ref "C91") (pin "1") (pinfunction "1_1") (pintype "passive"))
      (node (ref "C92") (pin "2") (pinfunction "2_2") (pintype "passive"))
      (node (ref "U5") (pin "6") (pinfunction "COMP_6") (pintype "output"))
    )
    (net (code "45") (name "Net-(U5-EN)") (class "Default")
      (node (ref "R25") (pin "1") (pinfunction "1_1") (pintype "passive"))
      (node (ref "R43") (pin "2") (pinfunction "2_2") (pintype "passive"))
      (node (ref "U5") (pin "3") (pinfunction "EN_3") (pintype "input"))
    )
    (net (code "46") (name "Net-(U5-SS)") (class "Default")
      (node (ref "C93") (pin "2") (pinfunction "2_2") (pintype "passive"))
      (node (ref "U5") (pin "4") (pinfunction "SS_4") (pintype "input"))
    )
    (net (code "47") (name "Net-(U5-VSENSE)") (class "Default")
      (node (ref "R45") (pin "2") (pinfunction "2_2") (pintype "passive"))
      (node (ref "R46") (pin "1") (pinfunction "1_1") (pintype "passive"))
      (node (ref "U5") (pin "5") (pinfunction "VSENSE_5") (pintype "input"))
    )
    (net (code "48") (name "unconnected-(IC38-NC-Pad1)") (class "Default")
      (node (ref "IC38") (pin "1") (pinfunction "NC_1") (pintype "passive"))
    )
    (net (code "49") (name "unconnected-(IC39-NC-Pad1)") (class "Default")
      (node (ref "IC39") (pin "1") (pinfunction "NC_1") (pintype "passive"))
    )
    (net (code "50") (name "unconnected-(IC40-NC-Pad1)") (class "Default")
      (node (ref "IC40") (pin "1") (pinfunction "NC_1") (pintype "passive"))
    )
    (net (code "51") (name "unconnected-(IC41-NC-Pad1)") (class "Default")
      (node (ref "IC41") (pin "1") (pinfunction "NC_1") (pintype "passive"))
    )
  )
)
